# control_unit.net
KiCad netlist of a schematic drawn in Altium Designer
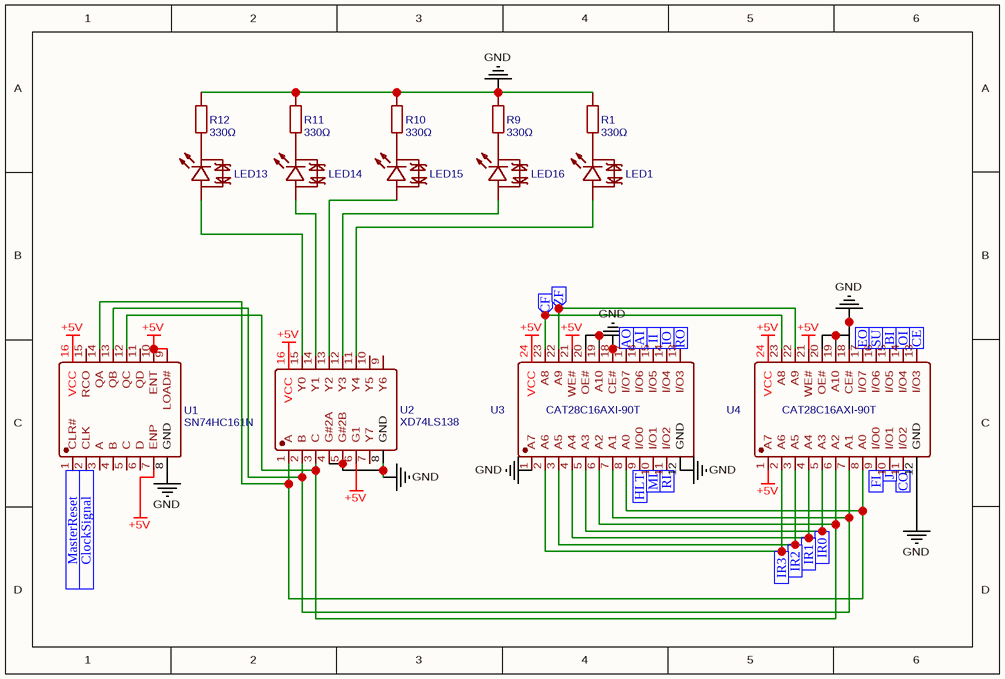
[diagram p0: control_unit.schdoc]

(export (version "E")
  (design (tool "Eeschema 10.0.6"))
  (components
    (comp (ref "LED1")
      (value "204-15UTC/S400-X9-L")
      (fields (field (name "MANUFACTURER") "EVERLIGHT(亿光)") (field (name "CONTRIBUTOR") "LCSC"))
      (libsource (lib "altium-import") (part "root_1_204-15UTC/S400-X9-L_"))
    )
    (comp (ref "LED13")
      (value "204-15UTC/S400-X9-L")
      (fields (field (name "MANUFACTURER") "EVERLIGHT(亿光)") (field (name "CONTRIBUTOR") "LCSC"))
      (libsource (lib "altium-import") (part "root_1_204-15UTC/S400-X9-L_"))
    )
    (comp (ref "LED14")
      (value "204-15UTC/S400-X9-L")
      (fields (field (name "MANUFACTURER") "EVERLIGHT(亿光)") (field (name "CONTRIBUTOR") "LCSC"))
      (libsource (lib "altium-import") (part "root_1_204-15UTC/S400-X9-L_"))
    )
    (comp (ref "LED15")
      (value "204-15UTC/S400-X9-L")
      (fields (field (name "MANUFACTURER") "EVERLIGHT(亿光)") (field (name "CONTRIBUTOR") "LCSC"))
      (libsource (lib "altium-import") (part "root_1_204-15UTC/S400-X9-L_"))
    )
    (comp (ref "LED16")
      (value "204-15UTC/S400-X9-L")
      (fields (field (name "MANUFACTURER") "EVERLIGHT(亿光)") (field (name "CONTRIBUTOR") "LCSC"))
      (libsource (lib "altium-import") (part "root_1_204-15UTC/S400-X9-L_"))
    )
    (comp (ref "R1")
      (value "330Ω")
      (fields
        (field (name "MANUFACTURER") "CCO(千志电子)")
        (field (name "MANUFACTURER PART") "MF1/2W-0.1Ω±1% T")
        (field (name "CONTRIBUTOR") "LCSC")
      )
      (libsource (lib "altium-import") (part "root_1_330Ω_"))
    )
    (comp (ref "R9")
      (value "330Ω")
      (fields
        (field (name "MANUFACTURER") "CCO(千志电子)")
        (field (name "MANUFACTURER PART") "MF1/2W-0.1Ω±1% T")
        (field (name "CONTRIBUTOR") "LCSC")
      )
      (libsource (lib "altium-import") (part "root_1_330Ω_"))
    )
    (comp (ref "R10")
      (value "330Ω")
      (fields
        (field (name "MANUFACTURER") "CCO(千志电子)")
        (field (name "MANUFACTURER PART") "MF1/2W-0.1Ω±1% T")
        (field (name "CONTRIBUTOR") "LCSC")
      )
      (libsource (lib "altium-import") (part "root_1_330Ω_"))
    )
    (comp (ref "R11")
      (value "330Ω")
      (fields
        (field (name "MANUFACTURER") "CCO(千志电子)")
        (field (name "MANUFACTURER PART") "MF1/2W-0.1Ω±1% T")
        (field (name "CONTRIBUTOR") "LCSC")
      )
      (libsource (lib "altium-import") (part "root_1_330Ω_"))
    )
    (comp (ref "R12")
      (value "330Ω")
      (fields
        (field (name "MANUFACTURER") "CCO(千志电子)")
        (field (name "MANUFACTURER PART") "MF1/2W-0.1Ω±1% T")
        (field (name "CONTRIBUTOR") "LCSC")
      )
      (libsource (lib "altium-import") (part "root_1_330Ω_"))
    )
    (comp (ref "U1")
      (value "SN74HC161N")
      (fields (field (name "MANUFACTURER") "TI(德州仪器)") (field (name "CONTRIBUTOR") "lcsc"))
      (libsource (lib "altium-import") (part "root_1_SN74HC161N_"))
    )
    (comp (ref "U2")
      (value "XD74LS138")
      (fields (field (name "MANUFACTURER") "XINLUDA(信路达)") (field (name "CONTRIBUTOR") "LCSC"))
      (libsource (lib "altium-import") (part "root_1_XD74LS138_"))
    )
    (comp (ref "U3")
      (value "CAT28C16AXI-90T")
      (fields (field (name "MANUFACTURER") "onsemi(安森美)") (field (name "CONTRIBUTOR") "lcsc"))
      (libsource (lib "altium-import") (part "root_1_CAT28C16AXI-90T_"))
    )
    (comp (ref "U4")
      (value "CAT28C16AXI-90T")
      (fields (field (name "MANUFACTURER") "onsemi(安森美)") (field (name "CONTRIBUTOR") "lcsc"))
      (libsource (lib "altium-import") (part "root_1_CAT28C16AXI-90T_"))
    )
  )
  (nets
    (net (code "1") (name "+5V") (class "Default")
      (node (ref "U1") (pin "10") (pinfunction "ENT_10") (pintype "passive"))
      (node (ref "U1") (pin "16") (pinfunction "VCC_16") (pintype "passive"))
      (node (ref "U1") (pin "7") (pinfunction "ENP_7") (pintype "passive"))
      (node (ref "U1") (pin "9") (pinfunction "LOAD#_9") (pintype "passive"))
      (node (ref "U2") (pin "16") (pinfunction "VCC_16") (pintype "passive"))
      (node (ref "U2") (pin "6") (pinfunction "G1_6") (pintype "passive"))
      (node (ref "U3") (pin "21") (pinfunction "WE#_21") (pintype "passive"))
      (node (ref "U3") (pin "24") (pinfunction "VCC_24") (pintype "passive"))
      (node (ref "U4") (pin "1") (pinfunction "A7_1") (pintype "passive"))
      (node (ref "U4") (pin "21") (pinfunction "WE#_21") (pintype "passive"))
      (node (ref "U4") (pin "24") (pinfunction "VCC_24") (pintype "passive"))
    )
    (net (code "2") (name "/AI") (class "Default")
      (node (ref "U3") (pin "16") (pinfunction "I/O6_16") (pintype "passive"))
    )
    (net (code "3") (name "/AO") (class "Default")
      (node (ref "U3") (pin "17") (pinfunction "I/O7_17") (pintype "passive"))
    )
    (net (code "4") (name "/BI") (class "Default")
      (node (ref "U4") (pin "15") (pinfunction "I/O5_15") (pintype "passive"))
    )
    (net (code "5") (name "/CE") (class "Default")
      (node (ref "U4") (pin "13") (pinfunction "I/O3_13") (pintype "passive"))
    )
    (net (code "6") (name "/CF") (class "Default")
      (node (ref "U3") (pin "23") (pinfunction "A8_23") (pintype "passive"))
      (node (ref "U4") (pin "23") (pinfunction "A8_23") (pintype "passive"))
    )
    (net (code "7") (name "/CO") (class "Default")
      (node (ref "U4") (pin "11") (pinfunction "I/O2_11") (pintype "passive"))
    )
    (net (code "8") (name "/ClockSignal") (class "Default")
      (node (ref "U1") (pin "2") (pinfunction "CLK_2") (pintype "passive"))
    )
    (net (code "9") (name "/EO") (class "Default")
      (node (ref "U4") (pin "17") (pinfunction "I/O7_17") (pintype "passive"))
    )
    (net (code "10") (name "/FI") (class "Default")
      (node (ref "U4") (pin "9") (pinfunction "I/O0_9") (pintype "passive"))
    )
    (net (code "11") (name "/HLT") (class "Default")
      (node (ref "U3") (pin "9") (pinfunction "I/O0_9") (pintype "passive"))
    )
    (net (code "12") (name "/II") (class "Default")
      (node (ref "U3") (pin "15") (pinfunction "I/O5_15") (pintype "passive"))
    )
    (net (code "13") (name "/IO") (class "Default")
      (node (ref "U3") (pin "14") (pinfunction "I/O4_14") (pintype "passive"))
    )
    (net (code "14") (name "/IR0") (class "Default")
      (node (ref "U3") (pin "5") (pinfunction "A3_5") (pintype "passive"))
      (node (ref "U4") (pin "5") (pinfunction "A3_5") (pintype "passive"))
    )
    (net (code "15") (name "/IR1") (class "Default")
      (node (ref "U3") (pin "4") (pinfunction "A4_4") (pintype "passive"))
      (node (ref "U4") (pin "4") (pinfunction "A4_4") (pintype "passive"))
    )
    (net (code "16") (name "/IR2") (class "Default")
      (node (ref "U3") (pin "3") (pinfunction "A5_3") (pintype "passive"))
      (node (ref "U4") (pin "3") (pinfunction "A5_3") (pintype "passive"))
    )
    (net (code "17") (name "/IR3") (class "Default")
      (node (ref "U3") (pin "2") (pinfunction "A6_2") (pintype "passive"))
      (node (ref "U4") (pin "2") (pinfunction "A6_2") (pintype "passive"))
    )
    (net (code "18") (name "/J") (class "Default")
      (node (ref "U4") (pin "10") (pinfunction "I/O1_10") (pintype "passive"))
    )
    (net (code "19") (name "/MI") (class "Default")
      (node (ref "U3") (pin "10") (pinfunction "I/O1_10") (pintype "passive"))
    )
    (net (code "20") (name "/MasterReset") (class "Default")
      (node (ref "U1") (pin "1") (pinfunction "CLR#_1") (pintype "passive"))
    )
    (net (code "21") (name "/OI") (class "Default")
      (node (ref "U4") (pin "14") (pinfunction "I/O4_14") (pintype "passive"))
    )
    (net (code "22") (name "/RI") (class "Default")
      (node (ref "U3") (pin "11") (pinfunction "I/O2_11") (pintype "passive"))
    )
    (net (code "23") (name "/RO") (class "Default")
      (node (ref "U3") (pin "13") (pinfunction "I/O3_13") (pintype "passive"))
    )
    (net (code "24") (name "/SU") (class "Default")
      (node (ref "U4") (pin "16") (pinfunction "I/O6_16") (pintype "passive"))
    )
    (net (code "25") (name "/ZF") (class "Default")
      (node (ref "U3") (pin "22") (pinfunction "A9_22") (pintype "passive"))
      (node (ref "U4") (pin "22") (pinfunction "A9_22") (pintype "passive"))
    )
    (net (code "26") (name "GND") (class "Default")
      (node (ref "R1") (pin "2") (pinfunction "2_2") (pintype "passive"))
      (node (ref "R10") (pin "2") (pinfunction "2_2") (pintype "passive"))
      (node (ref "R11") (pin "2") (pinfunction "2_2") (pintype "passive"))
      (node (ref "R12") (pin "2") (pinfunction "2_2") (pintype "passive"))
      (node (ref "R9") (pin "2") (pinfunction "2_2") (pintype "passive"))
      (node (ref "U1") (pin "8") (pinfunction "GND_8") (pintype "passive"))
      (node (ref "U2") (pin "4") (pinfunction "G#2A_4") (pintype "passive"))
      (node (ref "U2") (pin "5") (pinfunction "G#2B_5") (pintype "passive"))
      (node (ref "U2") (pin "8") (pinfunction "GND_8") (pintype "passive"))
      (node (ref "U3") (pin "1") (pinfunction "A7_1") (pintype "passive"))
      (node (ref "U3") (pin "12") (pinfunction "GND_12") (pintype "passive"))
      (node (ref "U3") (pin "18") (pinfunction "CE#_18") (pintype "passive"))
      (node (ref "U3") (pin "19") (pinfunction "A10_19") (pintype "passive"))
      (node (ref "U3") (pin "20") (pinfunction "OE#_20") (pintype "passive"))
      (node (ref "U4") (pin "12") (pinfunction "GND_12") (pintype "passive"))
      (node (ref "U4") (pin "18") (pinfunction "CE#_18") (pintype "passive"))
      (node (ref "U4") (pin "19") (pinfunction "A10_19") (pintype "passive"))
      (node (ref "U4") (pin "20") (pinfunction "OE#_20") (pintype "passive"))
    )
    (net (code "27") (name "Net-(LED1-A)") (class "Default")
      (node (ref "LED1") (pin "1") (pinfunction "A_1") (pintype "passive"))
      (node (ref "U2") (pin "11") (pinfunction "Y4_11") (pintype "passive"))
    )
    (net (code "28") (name "Net-(LED1-C)") (class "Default")
      (node (ref "LED1") (pin "2") (pinfunction "C_2") (pintype "passive"))
      (node (ref "R1") (pin "1") (pinfunction "1_1") (pintype "passive"))
    )
    (net (code "29") (name "Net-(LED13-A)") (class "Default")
      (node (ref "LED13") (pin "1") (pinfunction "A_1") (pintype "passive"))
      (node (ref "U2") (pin "15") (pinfunction "Y0_15") (pintype "passive"))
    )
    (net (code "30") (name "Net-(LED13-C)") (class "Default")
      (node (ref "LED13") (pin "2") (pinfunction "C_2") (pintype "passive"))
      (node (ref "R12") (pin "1") (pinfunction "1_1") (pintype "passive"))
    )
    (net (code "31") (name "Net-(LED14-A)") (class "Default")
      (node (ref "LED14") (pin "1") (pinfunction "A_1") (pintype "passive"))
      (node (ref "U2") (pin "14") (pinfunction "Y1_14") (pintype "passive"))
    )
    (net (code "32") (name "Net-(LED14-C)") (class "Default")
      (node (ref "LED14") (pin "2") (pinfunction "C_2") (pintype "passive"))
      (node (ref "R11") (pin "1") (pinfunction "1_1") (pintype "passive"))
    )
    (net (code "33") (name "Net-(LED15-A)") (class "Default")
      (node (ref "LED15") (pin "1") (pinfunction "A_1") (pintype "passive"))
      (node (ref "U2") (pin "13") (pinfunction "Y2_13") (pintype "passive"))
    )
    (net (code "34") (name "Net-(LED15-C)") (class "Default")
      (node (ref "LED15") (pin "2") (pinfunction "C_2") (pintype "passive"))
      (node (ref "R10") (pin "1") (pinfunction "1_1") (pintype "passive"))
    )
    (net (code "35") (name "Net-(LED16-A)") (class "Default")
      (node (ref "LED16") (pin "1") (pinfunction "A_1") (pintype "passive"))
      (node (ref "U2") (pin "12") (pinfunction "Y3_12") (pintype "passive"))
    )
    (net (code "36") (name "Net-(LED16-C)") (class "Default")
      (node (ref "LED16") (pin "2") (pinfunction "C_2") (pintype "passive"))
      (node (ref "R9") (pin "1") (pinfunction "1_1") (pintype "passive"))
    )
    (net (code "37") (name "Net-(U1-QA)") (class "Default")
      (node (ref "U1") (pin "14") (pinfunction "QA_14") (pintype "passive"))
      (node (ref "U2") (pin "1") (pinfunction "A_1") (pintype "passive"))
      (node (ref "U3") (pin "8") (pinfunction "A0_8") (pintype "passive"))
      (node (ref "U4") (pin "8") (pinfunction "A0_8") (pintype "passive"))
    )
    (net (code "38") (name "Net-(U1-QB)") (class "Default")
      (node (ref "U1") (pin "13") (pinfunction "QB_13") (pintype "passive"))
      (node (ref "U2") (pin "2") (pinfunction "B_2") (pintype "passive"))
      (node (ref "U3") (pin "7") (pinfunction "A1_7") (pintype "passive"))
      (node (ref "U4") (pin "7") (pinfunction "A1_7") (pintype "passive"))
    )
    (net (code "39") (name "Net-(U1-QC)") (class "Default")
      (node (ref "U1") (pin "12") (pinfunction "QC_12") (pintype "passive"))
      (node (ref "U2") (pin "3") (pinfunction "C_3") (pintype "passive"))
      (node (ref "U3") (pin "6") (pinfunction "A2_6") (pintype "passive"))
      (node (ref "U4") (pin "6") (pinfunction "A2_6") (pintype "passive"))
    )
    (net (code "40") (name "unconnected-(U1-A-Pad3)") (class "Default")
      (node (ref "U1") (pin "3") (pinfunction "A_3") (pintype "passive"))
    )
    (net (code "41") (name "unconnected-(U1-B-Pad4)") (class "Default")
      (node (ref "U1") (pin "4") (pinfunction "B_4") (pintype "passive"))
    )
    (net (code "42") (name "unconnected-(U1-C-Pad5)") (class "Default")
      (node (ref "U1") (pin "5") (pinfunction "C_5") (pintype "passive"))
    )
    (net (code "43") (name "unconnected-(U1-D-Pad6)") (class "Default")
      (node (ref "U1") (pin "6") (pinfunction "D_6") (pintype "passive"))
    )
    (net (code "44") (name "unconnected-(U1-QD-Pad11)") (class "Default")
      (node (ref "U1") (pin "11") (pinfunction "QD_11") (pintype "passive"))
    )
    (net (code "45") (name "unconnected-(U1-RCO-Pad15)") (class "Default")
      (node (ref "U1") (pin "15") (pinfunction "RCO_15") (pintype "passive"))
    )
    (net (code "46") (name "unconnected-(U2-Y5-Pad10)") (class "Default")
      (node (ref "U2") (pin "10") (pinfunction "Y5_10") (pintype "passive"))
    )
    (net (code "47") (name "unconnected-(U2-Y6-Pad9)") (class "Default")
      (node (ref "U2") (pin "9") (pinfunction "Y6_9") (pintype "passive"))
    )
    (net (code "48") (name "unconnected-(U2-Y7-Pad7)") (class "Default")
      (node (ref "U2") (pin "7") (pinfunction "Y7_7") (pintype "passive"))
    )
  )
)
